# shinobi_grideye.net
KiCad netlist of a schematic drawn in EAGLE
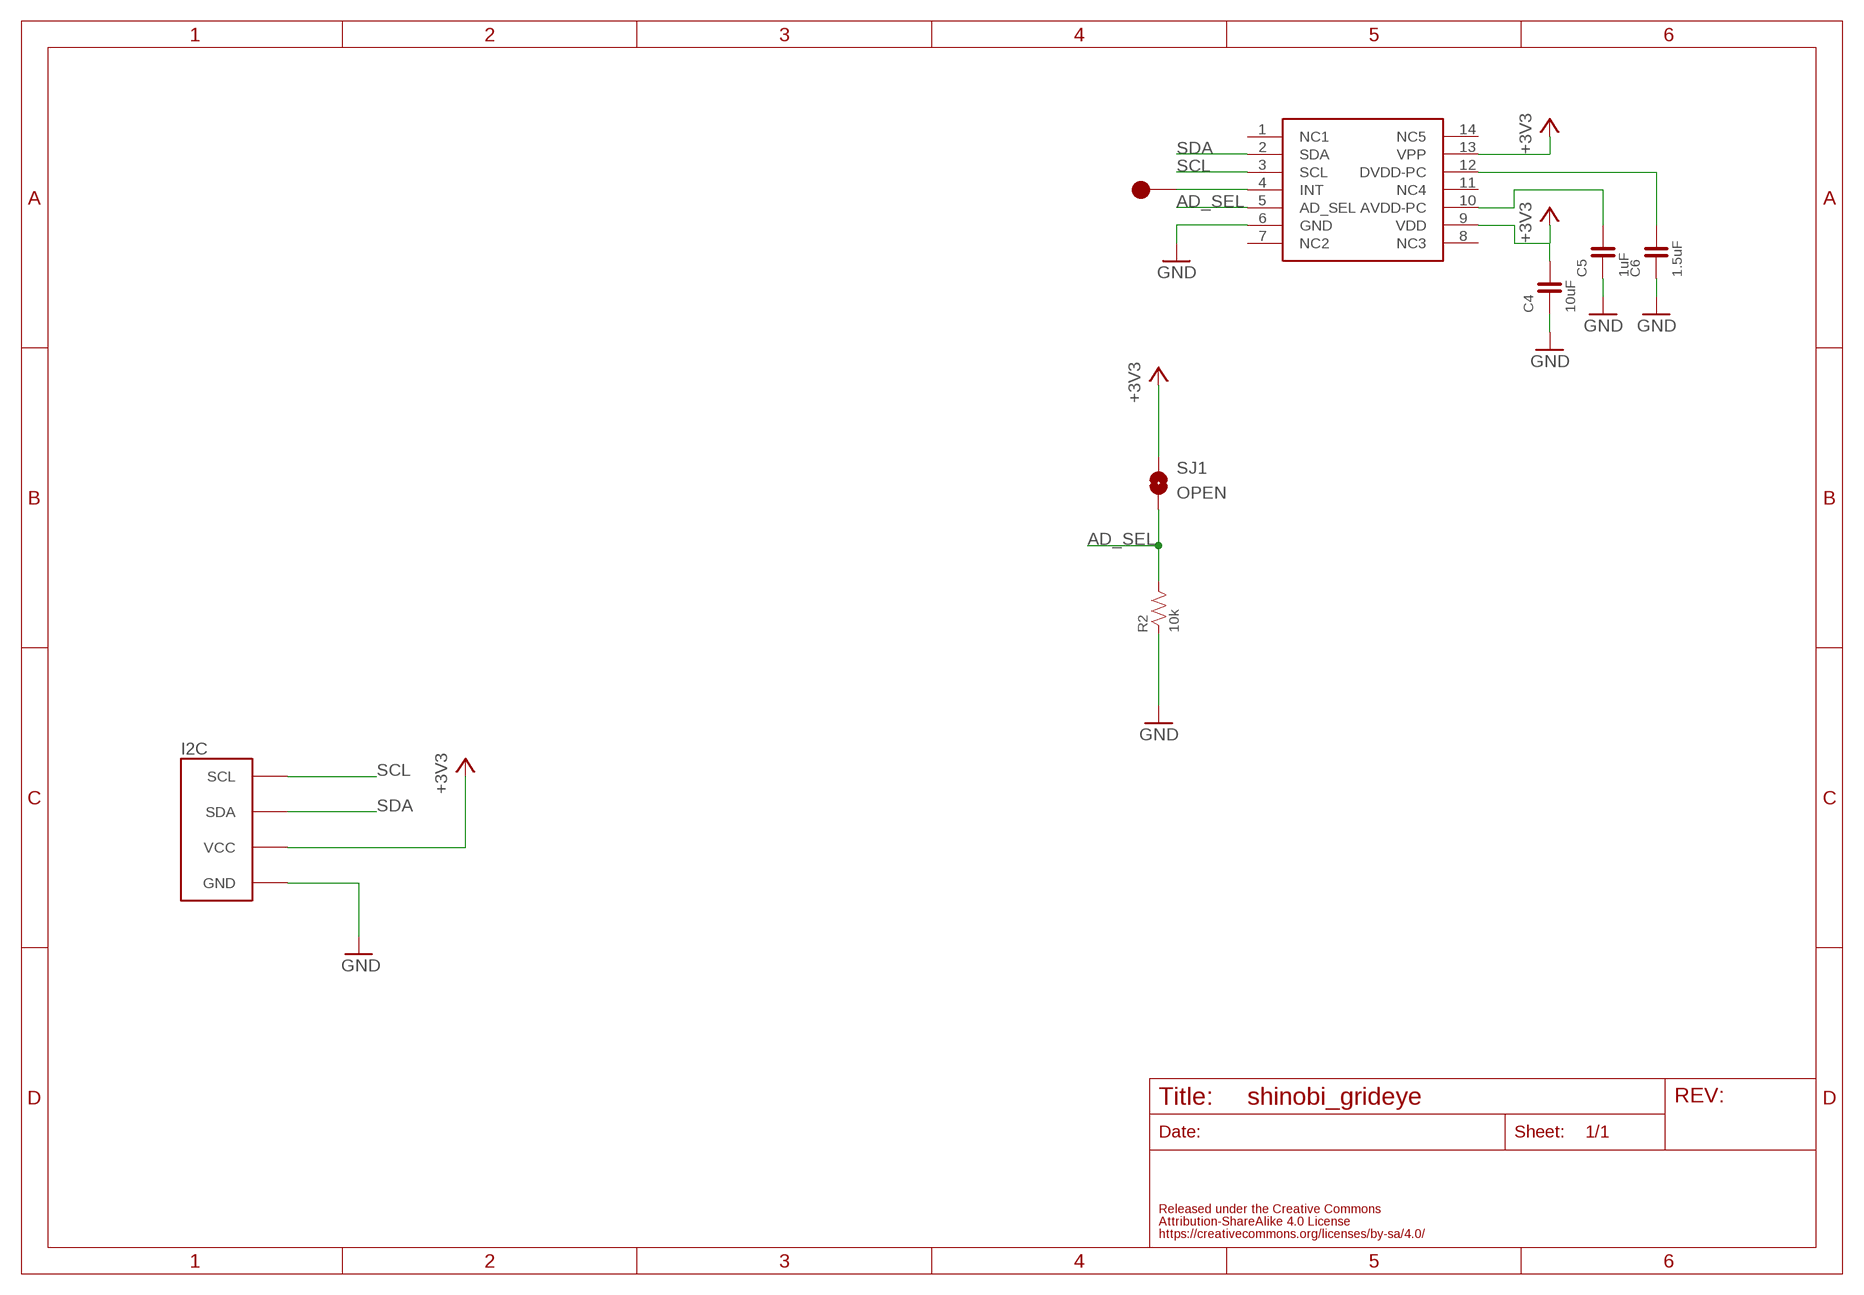
[diagram p0: schematic, sheet 1]

(export (version "E")
  (design (tool "Eeschema 10.0.6"))
  (components
    (comp (ref "C4")
      (value "10uF")
      (footprint "eagle-import:0603")
      (libsource (lib "eagle-import") (part "CAPACITOR-0603"))
    )
    (comp (ref "C5")
      (value "1uF")
      (footprint "eagle-import:0603")
      (libsource (lib "eagle-import") (part "CAPACITOR-0603"))
    )
    (comp (ref "C6")
      (value "1.5uF")
      (footprint "eagle-import:0603")
      (libsource (lib "eagle-import") (part "CAPACITOR-0603"))
    )
    (comp (ref "GRIDEYE")
      (value "PN-AMG8331")
      (footprint "eagle-import:PANASONIC-AMG8831")
      (libsource (lib "eagle-import") (part "PN-AMG8331"))
    )
    (comp (ref "I2C")
      (value "FABO_BRICK_I2C-S04B-PASK-2_LONG")
      (footprint "eagle-import:FABO_BRICK_I2C_S04B-PASK-2_LONG")
      (libsource (lib "eagle-import") (part "FABO_BRICK_I2C-S04B-PASK-2_LONG"))
    )
    (comp (ref "INT")
      (value "INT")
      (footprint "eagle-import:TP-15")
      (libsource (lib "eagle-import") (part "TP-15"))
    )
    (comp (ref "R2")
      (value "10k")
      (footprint "eagle-import:0603")
      (libsource (lib "eagle-import") (part "RESISTOR-0603"))
    )
    (comp (ref "SJ1")
      (value "OPEN")
      (footprint "eagle-import:SMD-JUMPER-2-OPEN")
      (libsource (lib "eagle-import") (part "SMD-JUMPER-2-OPEN"))
    )
  )
  (nets
    (net (code "1") (name "+3V3") (class "Default")
      (node (ref "C4") (pin "2") (pinfunction "2_2") (pintype "passive"))
      (node (ref "GRIDEYE") (pin "13") (pinfunction "VPP_13") (pintype "bidirectional"))
      (node (ref "GRIDEYE") (pin "9") (pinfunction "VDD_9") (pintype "bidirectional"))
      (node (ref "I2C") (pin "VCC") (pinfunction "VCC_VCC") (pintype "bidirectional"))
      (node (ref "SJ1") (pin "1") (pinfunction "1_1") (pintype "passive"))
    )
    (net (code "2") (name "/AD_SEL") (class "Default")
      (node (ref "GRIDEYE") (pin "5") (pinfunction "AD_SEL_5") (pintype "bidirectional"))
      (node (ref "R2") (pin "2") (pinfunction "2_2") (pintype "bidirectional"))
      (node (ref "SJ1") (pin "2") (pinfunction "2_2") (pintype "passive"))
    )
    (net (code "3") (name "/SCL") (class "Default")
      (node (ref "GRIDEYE") (pin "3") (pinfunction "SCL_3") (pintype "bidirectional"))
      (node (ref "I2C") (pin "SCL") (pinfunction "SCL_SCL") (pintype "bidirectional"))
    )
    (net (code "4") (name "/SDA") (class "Default")
      (node (ref "GRIDEYE") (pin "2") (pinfunction "SDA_2") (pintype "bidirectional"))
      (node (ref "I2C") (pin "SDA") (pinfunction "SDA_SDA") (pintype "bidirectional"))
    )
    (net (code "5") (name "GND") (class "Default")
      (node (ref "C4") (pin "1") (pinfunction "1_1") (pintype "passive"))
      (node (ref "C5") (pin "1") (pinfunction "1_1") (pintype "passive"))
      (node (ref "C6") (pin "1") (pinfunction "1_1") (pintype "passive"))
      (node (ref "GRIDEYE") (pin "6") (pinfunction "GND_6") (pintype "bidirectional"))
      (node (ref "I2C") (pin "GND") (pinfunction "GND_GND") (pintype "bidirectional"))
      (node (ref "R2") (pin "1") (pinfunction "1_1") (pintype "bidirectional"))
    )
    (net (code "6") (name "Net-(GRIDEYE-AVDD-PC)") (class "Default")
      (node (ref "C5") (pin "2") (pinfunction "2_2") (pintype "passive"))
      (node (ref "GRIDEYE") (pin "10") (pinfunction "AVDD-PC_10") (pintype "bidirectional"))
    )
    (net (code "7") (name "Net-(GRIDEYE-DVDD-PC)") (class "Default")
      (node (ref "C6") (pin "2") (pinfunction "2_2") (pintype "passive"))
      (node (ref "GRIDEYE") (pin "12") (pinfunction "DVDD-PC_12") (pintype "bidirectional"))
    )
    (net (code "8") (name "Net-(GRIDEYE-INT)") (class "Default")
      (node (ref "GRIDEYE") (pin "4") (pinfunction "INT_4") (pintype "bidirectional"))
      (node (ref "INT") (pin "1") (pinfunction "1_1") (pintype "bidirectional"))
    )
    (net (code "9") (name "unconnected-(GRIDEYE-NC1-Pad1)") (class "Default")
      (node (ref "GRIDEYE") (pin "1") (pinfunction "NC1_1") (pintype "bidirectional"))
    )
    (net (code "10") (name "unconnected-(GRIDEYE-NC2-Pad7)") (class "Default")
      (node (ref "GRIDEYE") (pin "7") (pinfunction "NC2_7") (pintype "bidirectional"))
    )
    (net (code "11") (name "unconnected-(GRIDEYE-NC3-Pad8)") (class "Default")
      (node (ref "GRIDEYE") (pin "8") (pinfunction "NC3_8") (pintype "bidirectional"))
    )
    (net (code "12") (name "unconnected-(GRIDEYE-NC4-Pad11)") (class "Default")
      (node (ref "GRIDEYE") (pin "11") (pinfunction "NC4_11") (pintype "bidirectional"))
    )
    (net (code "13") (name "unconnected-(GRIDEYE-NC5-Pad14)") (class "Default")
      (node (ref "GRIDEYE") (pin "14") (pinfunction "NC5_14") (pintype "bidirectional"))
    )
  )
)
